# DAC_MAX5841.net
KiCad netlist of a schematic drawn in Altium Designer
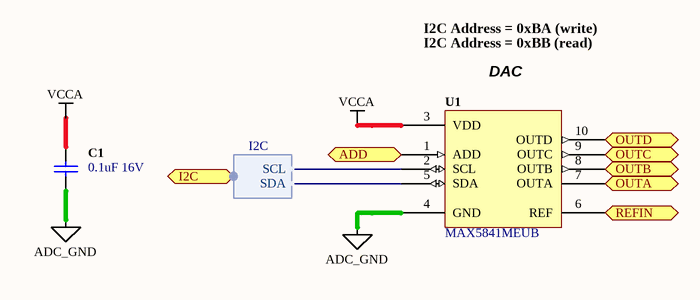
[diagram p0: DAC_MAX5841.SchDoc]

(export (version "E")
  (design (tool "Eeschema 10.0.6"))
  (components
    (comp (ref "C1")
      (value "0.1uF 16V")
      (footprint "CAPC1005-STAR")
      (description "Capacitor, Ceramic, 0.1uF 10% 16V 0402 (1005) X7R")
      (fields (field (name "TOLERANCE") "10 %"))
      (libsource (lib "altium-import") (part "root_0_CAP-NP_"))
    )
    (comp (ref "U1")
      (value "MAX5841MEUB")
      (footprint "TSSOP50P490-10")
      (description "MAX5841MEUB, Quad, 10-Bit, Low-Power, I2C, DAC")
      (libsource (lib "altium-import") (part "root_0_MAX5841_"))
    )
  )
  (nets
    (net (code "2") (name "/ADD") (class "Default")
      (node (ref "U1") (pin "1") (pinfunction "ADD_1") (pintype "input"))
    )
    (net (code "3") (name "/OUTA") (class "Default")
      (node (ref "U1") (pin "7") (pinfunction "OUTA_7") (pintype "passive"))
    )
    (net (code "4") (name "/OUTB") (class "Default")
      (node (ref "U1") (pin "8") (pinfunction "OUTB_8") (pintype "output"))
    )
    (net (code "5") (name "/OUTC") (class "Default")
      (node (ref "U1") (pin "9") (pinfunction "OUTC_9") (pintype "output"))
    )
    (net (code "6") (name "/OUTD") (class "Default")
      (node (ref "U1") (pin "10") (pinfunction "OUTD_10") (pintype "output"))
    )
    (net (code "7") (name "/REFIN") (class "Default")
      (node (ref "U1") (pin "6") (pinfunction "REF_6") (pintype "passive"))
    )
    (net (code "8") (name "/SCL") (class "Default")
      (node (ref "U1") (pin "2") (pinfunction "SCL_2") (pintype "bidirectional"))
    )
    (net (code "9") (name "/SDA") (class "Default")
      (node (ref "U1") (pin "5") (pinfunction "SDA_5") (pintype "bidirectional"))
    )
    (net (code "11") (name "ADC_GND") (class "Default")
      (node (ref "C1") (pin "2") (pinfunction "2_2") (pintype "passive"))
      (node (ref "U1") (pin "4") (pinfunction "GND_4") (pintype "power_in"))
    )
    (net (code "12") (name "VCCA") (class "Default")
      (node (ref "C1") (pin "1") (pinfunction "1_1") (pintype "passive"))
      (node (ref "U1") (pin "3") (pinfunction "VDD_3") (pintype "power_in"))
    )
  )
)
